# TIDA-01576_ADS8686S_ISO_Interface_Pg6-Le.net
KiCad netlist of a schematic drawn in Altium Designer
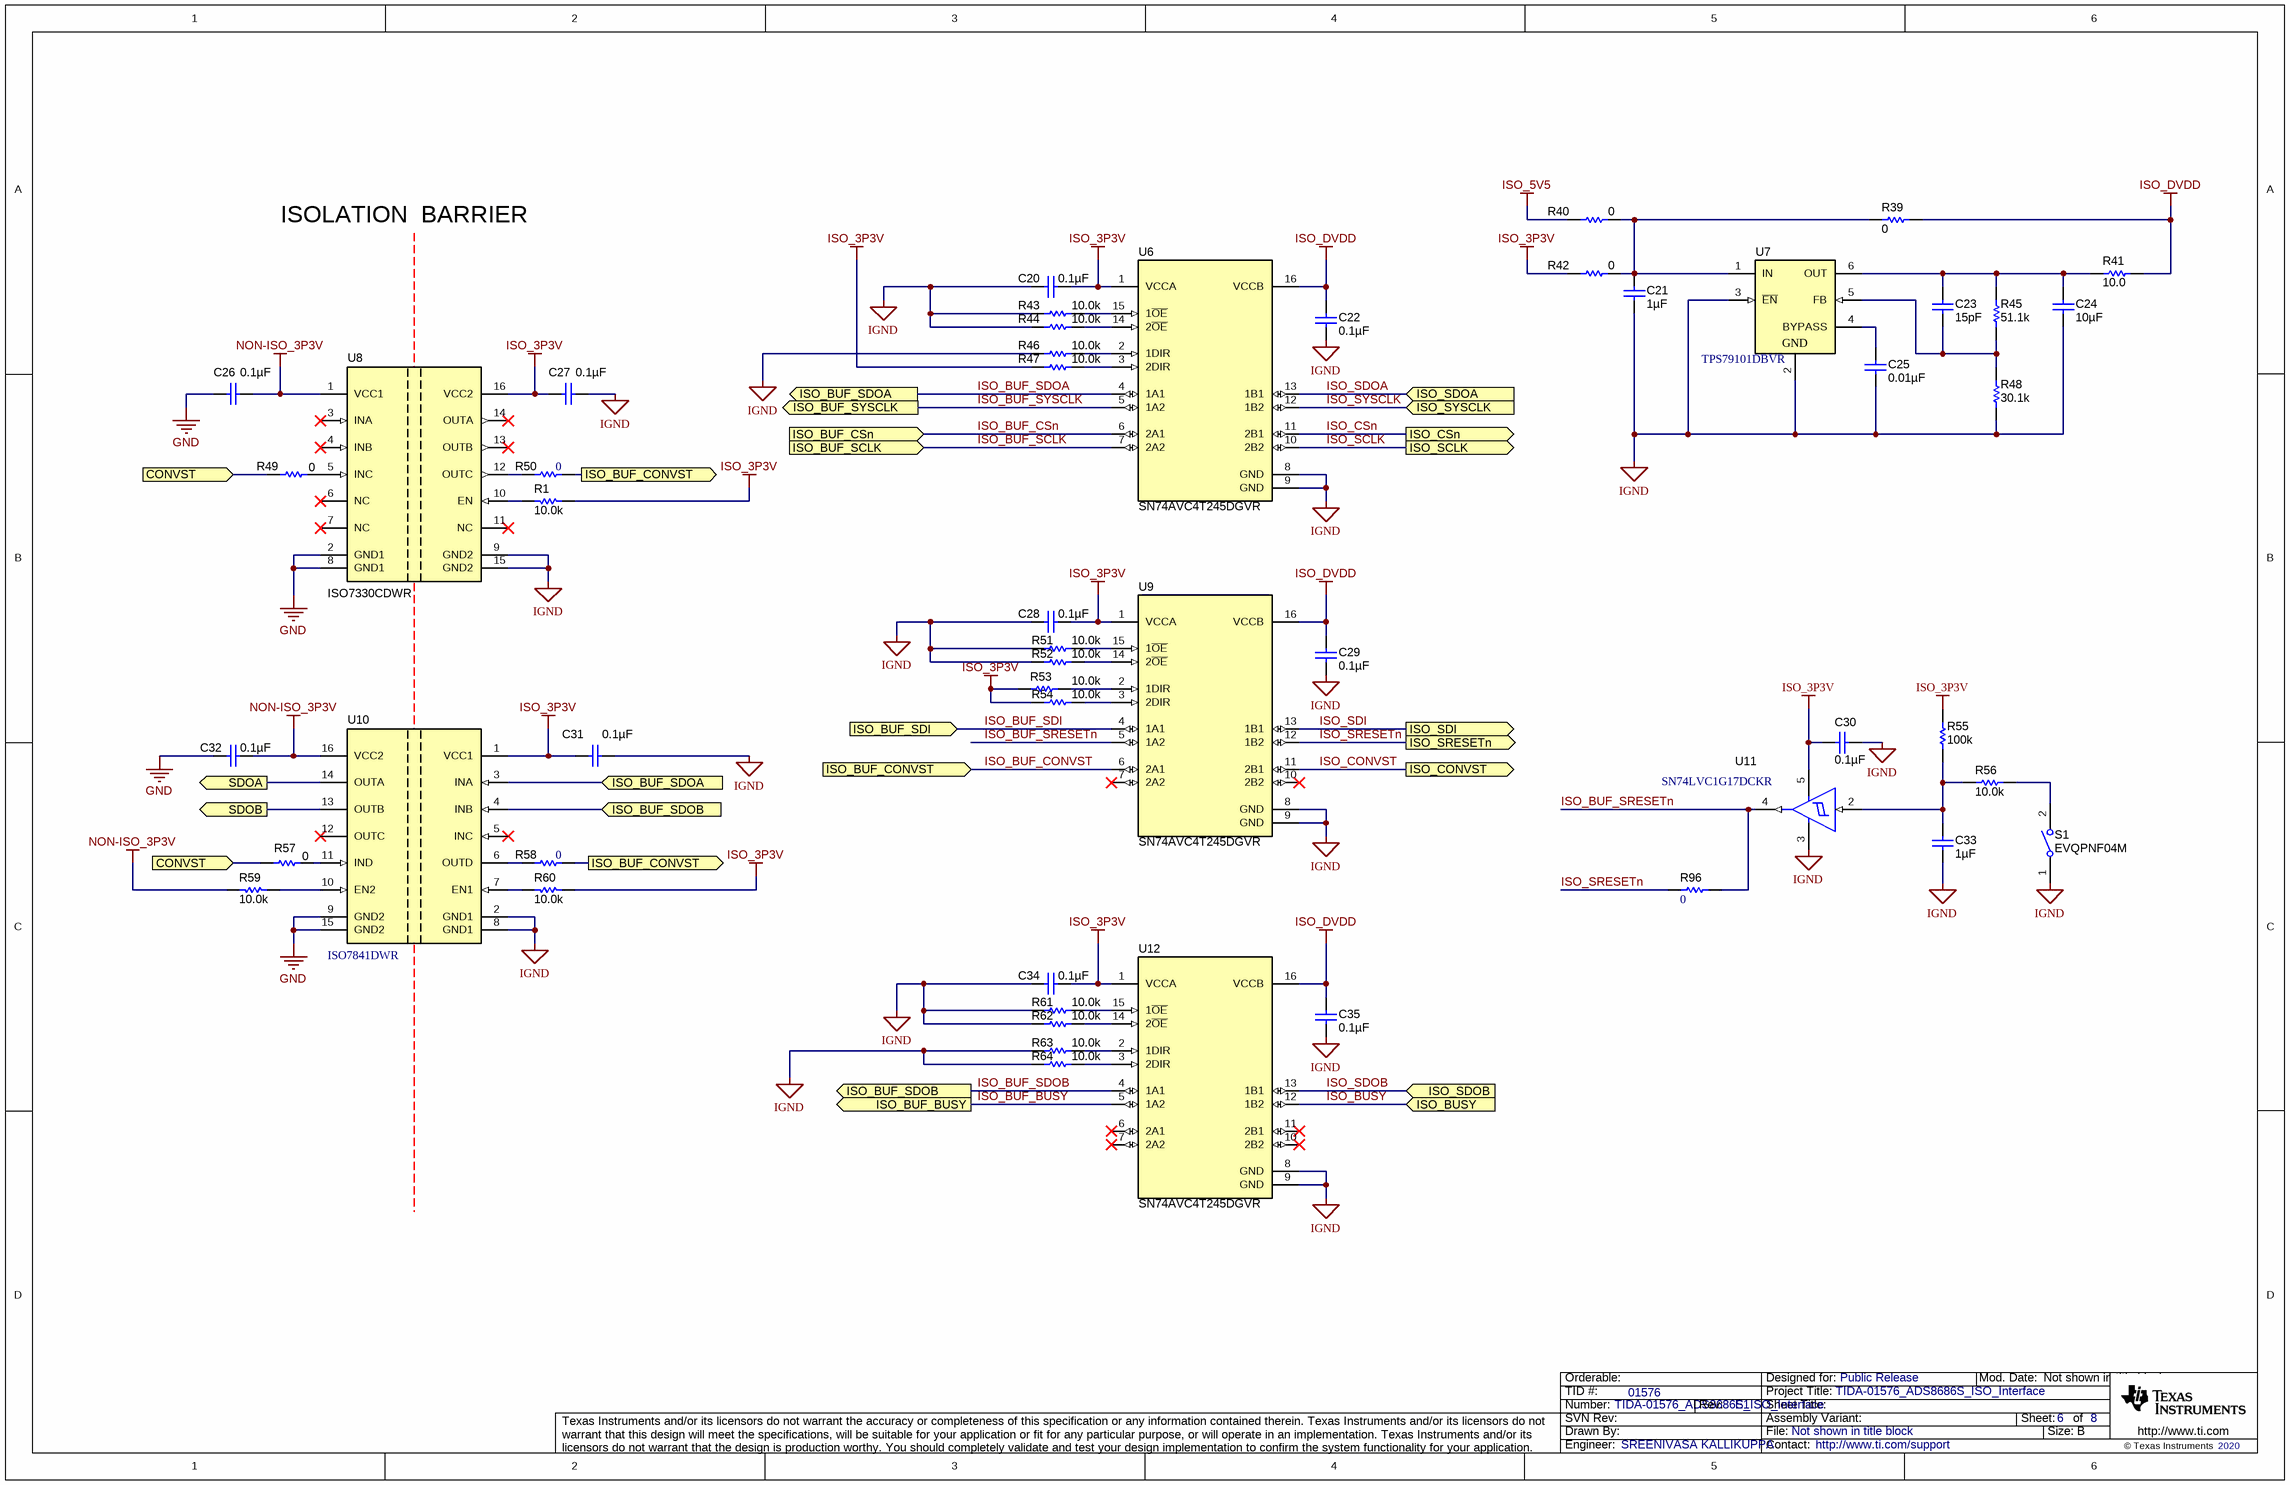
[diagram p0: TIDA-01576_ADS8686S_ISO_Interface_Pg6-LevelShifters.SchDoc]

(export (version "E")
  (design (tool "Eeschema 10.0.6"))
  (components
    (comp (ref "C20")
      (value "GRM155R71C104KA88D")
      (footprint "0402")
      (description "CAP, CERM, 0.1 µF, 16 V, +/- 10%, X7R, 0402")
      (fields
        (field (name "VALUEDISPLAYED") "0.1µF")
        (field (name "MANUFACTURER") "MuRata")
        (field (name "PUBLISHER") "Texas Instruments")
      )
      (libsource (lib "Capacitor_Ceramic") (part "GRM155R71C104KA88D"))
    )
    (comp (ref "C21")
      (value "GRM188R71E105KA12D")
      (footprint "0603")
      (description "CAP, CERM, 1 µF, 25 V, +/- 10%, X7R, 0603")
      (fields
        (field (name "VALUEDISPLAYED") "1µF")
        (field (name "MANUFACTURER") "MuRata")
        (field (name "PUBLISHER") "Texas Instruments")
      )
      (libsource (lib "Capacitor_Ceramic") (part "GRM188R71E105KA12D"))
    )
    (comp (ref "C22")
      (value "GRM155R71C104KA88D")
      (footprint "0402")
      (description "CAP, CERM, 0.1 µF, 16 V, +/- 10%, X7R, 0402")
      (fields
        (field (name "VALUEDISPLAYED") "0.1µF")
        (field (name "MANUFACTURER") "MuRata")
        (field (name "PUBLISHER") "Texas Instruments")
      )
      (libsource (lib "Capacitor_Ceramic") (part "GRM155R71C104KA88D"))
    )
    (comp (ref "C23")
      (value "GRM1885C1H150JA01D")
      (footprint "0603")
      (description "CAP, CERM, 15 pF, 50 V, +/- 5%, C0G/NP0, 0603")
      (fields
        (field (name "VALUEDISPLAYED") "15pF")
        (field (name "MANUFACTURER") "MuRata")
        (field (name "PUBLISHER") "Texas Instruments")
      )
      (libsource (lib "Capacitor_Ceramic") (part "GRM1885C1H150JA01D"))
    )
    (comp (ref "C24")
      (value "CL21B106KOQNNNE")
      (footprint "0805_HV")
      (description "CAP, CERM, 10 µF, 16 V, +/- 10%, X7R, 0805")
      (fields
        (field (name "VALUEDISPLAYED") "10µF")
        (field (name "MANUFACTURER") "Samsung Electro-Mechanics")
        (field (name "PUBLISHER") "Texas Instruments")
      )
      (libsource (lib "Capacitor_Ceramic") (part "CL21B106KOQNNNE"))
    )
    (comp (ref "C25")
      (value "GRM188R71E103KA01D")
      (footprint "0603")
      (description "CAP, CERM, 0.01 µF, 25 V, +/- 10%, X7R, 0603")
      (fields
        (field (name "VALUEDISPLAYED") "0.01µF")
        (field (name "MANUFACTURER") "MuRata")
        (field (name "PUBLISHER") "Texas Instruments")
      )
      (libsource (lib "Capacitor_Ceramic") (part "GRM188R71E103KA01D"))
    )
    (comp (ref "C26")
      (value "GRM155R71C104KA88D")
      (footprint "0402")
      (description "CAP, CERM, 0.1 µF, 16 V, +/- 10%, X7R, 0402")
      (fields
        (field (name "VALUEDISPLAYED") "0.1µF")
        (field (name "MANUFACTURER") "MuRata")
        (field (name "PUBLISHER") "Texas Instruments")
      )
      (libsource (lib "Capacitor_Ceramic") (part "GRM155R71C104KA88D"))
    )
    (comp (ref "C27")
      (value "GRM155R71C104KA88D")
      (footprint "0402")
      (description "CAP, CERM, 0.1 µF, 16 V, +/- 10%, X7R, 0402")
      (fields
        (field (name "VALUEDISPLAYED") "0.1µF")
        (field (name "MANUFACTURER") "MuRata")
        (field (name "PUBLISHER") "Texas Instruments")
      )
      (libsource (lib "Capacitor_Ceramic") (part "GRM155R71C104KA88D"))
    )
    (comp (ref "C28")
      (value "GRM155R71C104KA88D")
      (footprint "0402")
      (description "CAP, CERM, 0.1 µF, 16 V, +/- 10%, X7R, 0402")
      (fields
        (field (name "VALUEDISPLAYED") "0.1µF")
        (field (name "MANUFACTURER") "MuRata")
        (field (name "PUBLISHER") "Texas Instruments")
      )
      (libsource (lib "Capacitor_Ceramic") (part "GRM155R71C104KA88D"))
    )
    (comp (ref "C29")
      (value "GRM155R71C104KA88D")
      (footprint "0402")
      (description "CAP, CERM, 0.1 µF, 16 V, +/- 10%, X7R, 0402")
      (fields
        (field (name "VALUEDISPLAYED") "0.1µF")
        (field (name "MANUFACTURER") "MuRata")
        (field (name "PUBLISHER") "Texas Instruments")
      )
      (libsource (lib "Capacitor_Ceramic") (part "GRM155R71C104KA88D"))
    )
    (comp (ref "C30")
      (value "GRM155R71C104KA88D")
      (footprint "0402")
      (description "CAP, CERM, 0.1 µF, 16 V, +/- 10%, X7R, 0402")
      (fields
        (field (name "VALUEDISPLAYED") "0.1µF")
        (field (name "MANUFACTURER") "MuRata")
        (field (name "PUBLISHER") "Texas Instruments")
      )
      (libsource (lib "Capacitor_Ceramic") (part "GRM155R71C104KA88D"))
    )
    (comp (ref "C31")
      (value "GRM155R71C104KA88D")
      (footprint "0402")
      (description "CAP, CERM, 0.1 µF, 16 V, +/- 10%, X7R, 0402")
      (fields
        (field (name "VALUEDISPLAYED") "0.1µF")
        (field (name "MANUFACTURER") "MuRata")
        (field (name "PUBLISHER") "Texas Instruments")
      )
      (libsource (lib "Capacitor_Ceramic") (part "GRM155R71C104KA88D"))
    )
    (comp (ref "C32")
      (value "GRM155R71C104KA88D")
      (footprint "0402")
      (description "CAP, CERM, 0.1 µF, 16 V, +/- 10%, X7R, 0402")
      (fields
        (field (name "VALUEDISPLAYED") "0.1µF")
        (field (name "MANUFACTURER") "MuRata")
        (field (name "PUBLISHER") "Texas Instruments")
      )
      (libsource (lib "Capacitor_Ceramic") (part "GRM155R71C104KA88D"))
    )
    (comp (ref "C33")
      (value "GRM188R71E105KA12D")
      (footprint "0603")
      (description "CAP, CERM, 1 µF, 25 V, +/- 10%, X7R, 0603")
      (fields
        (field (name "VALUEDISPLAYED") "1µF")
        (field (name "MANUFACTURER") "MuRata")
        (field (name "PUBLISHER") "Texas Instruments")
      )
      (libsource (lib "Capacitor_Ceramic") (part "GRM188R71E105KA12D"))
    )
    (comp (ref "C34")
      (value "GRM155R71C104KA88D")
      (footprint "0402")
      (description "CAP, CERM, 0.1 µF, 16 V, +/- 10%, X7R, 0402")
      (fields
        (field (name "VALUEDISPLAYED") "0.1µF")
        (field (name "MANUFACTURER") "MuRata")
        (field (name "PUBLISHER") "Texas Instruments")
      )
      (libsource (lib "Capacitor_Ceramic") (part "GRM155R71C104KA88D"))
    )
    (comp (ref "C35")
      (value "GRM155R71C104KA88D")
      (footprint "0402")
      (description "CAP, CERM, 0.1 µF, 16 V, +/- 10%, X7R, 0402")
      (fields
        (field (name "VALUEDISPLAYED") "0.1µF")
        (field (name "MANUFACTURER") "MuRata")
        (field (name "PUBLISHER") "Texas Instruments")
      )
      (libsource (lib "Capacitor_Ceramic") (part "GRM155R71C104KA88D"))
    )
    (comp (ref "R1")
      (value "ERJ-2RKF1002X")
      (footprint "0402")
      (description "RES, 10.0 k, 1%, 0.1 W, 0402")
      (fields
        (field (name "VALUEDISPLAYED") "10.0k")
        (field (name "MANUFACTURER") "Panasonic")
        (field (name "PUBLISHER") "Texas Instruments")
      )
      (libsource (lib "Resistor_0402") (part "ERJ-2RKF1002X"))
    )
    (comp (ref "R39")
      (value "CRCW06030000Z0EA")
      (footprint "0603")
      (description "RES, 0, 5%, 0.1 W, 0603")
      (fields
        (field (name "VALUEDISPLAYED") "0")
        (field (name "MANUFACTURER") "Vishay-Dale")
        (field (name "PUBLISHER") "Texas Instruments")
      )
      (libsource (lib "Resistor_0603") (part "CRCW06030000Z0EA"))
    )
    (comp (ref "R40")
      (value "CRCW06030000Z0EA")
      (footprint "0603")
      (description "RES, 0, 5%, 0.1 W, 0603")
      (fields
        (field (name "VALUEDISPLAYED") "0")
        (field (name "MANUFACTURER") "Vishay-Dale")
        (field (name "PUBLISHER") "Texas Instruments")
      )
      (libsource (lib "Resistor_0603") (part "CRCW06030000Z0EA"))
    )
    (comp (ref "R41")
      (value "CRT0603-BY-10R0ELF")
      (footprint "0603")
      (description "RES, 10.0, 0.1%, 0.1 W, 0603")
      (fields
        (field (name "VALUEDISPLAYED") "10.0")
        (field (name "MANUFACTURER") "Bourns")
        (field (name "PUBLISHER") "Texas Instruments")
      )
      (libsource (lib "Resistor_0603") (part "CRT0603-BY-10R0ELF"))
    )
    (comp (ref "R42")
      (value "CRCW06030000Z0EA")
      (footprint "0603")
      (description "RES, 0, 5%, 0.1 W, 0603")
      (fields
        (field (name "VALUEDISPLAYED") "0")
        (field (name "MANUFACTURER") "Vishay-Dale")
        (field (name "PUBLISHER") "Texas Instruments")
      )
      (libsource (lib "Resistor_0603") (part "CRCW06030000Z0EA"))
    )
    (comp (ref "R43")
      (value "ERJ-2RKF1002X")
      (footprint "0402")
      (description "RES, 10.0 k, 1%, 0.1 W, 0402")
      (fields
        (field (name "VALUEDISPLAYED") "10.0k")
        (field (name "MANUFACTURER") "Panasonic")
        (field (name "PUBLISHER") "Texas Instruments")
      )
      (libsource (lib "Resistor_0402") (part "ERJ-2RKF1002X"))
    )
    (comp (ref "R44")
      (value "ERJ-2RKF1002X")
      (footprint "0402")
      (description "RES, 10.0 k, 1%, 0.1 W, 0402")
      (fields
        (field (name "VALUEDISPLAYED") "10.0k")
        (field (name "MANUFACTURER") "Panasonic")
        (field (name "PUBLISHER") "Texas Instruments")
      )
      (libsource (lib "Resistor_0402") (part "ERJ-2RKF1002X"))
    )
    (comp (ref "R45")
      (value "CRCW060351K1FKEA")
      (footprint "0603")
      (description "RES, 51.1 k, 1%, 0.1 W, 0603")
      (fields
        (field (name "VALUEDISPLAYED") "51.1k")
        (field (name "MANUFACTURER") "Vishay-Dale")
        (field (name "PUBLISHER") "Texas Instruments")
      )
      (libsource (lib "Resistor_0603") (part "CRCW060351K1FKEA"))
    )
    (comp (ref "R46")
      (value "ERJ-2RKF1002X")
      (footprint "0402")
      (description "RES, 10.0 k, 1%, 0.1 W, 0402")
      (fields
        (field (name "VALUEDISPLAYED") "10.0k")
        (field (name "MANUFACTURER") "Panasonic")
        (field (name "PUBLISHER") "Texas Instruments")
      )
      (libsource (lib "Resistor_0402") (part "ERJ-2RKF1002X"))
    )
    (comp (ref "R47")
      (value "ERJ-2RKF1002X")
      (footprint "0402")
      (description "RES, 10.0 k, 1%, 0.1 W, 0402")
      (fields
        (field (name "VALUEDISPLAYED") "10.0k")
        (field (name "MANUFACTURER") "Panasonic")
        (field (name "PUBLISHER") "Texas Instruments")
      )
      (libsource (lib "Resistor_0402") (part "ERJ-2RKF1002X"))
    )
    (comp (ref "R48")
      (value "CRCW060330K1FKEA")
      (footprint "0603")
      (description "RES, 30.1 k, 1%, 0.1 W, 0603")
      (fields
        (field (name "VALUEDISPLAYED") "30.1k")
        (field (name "MANUFACTURER") "Vishay-Dale")
        (field (name "PUBLISHER") "Texas Instruments")
      )
      (libsource (lib "Resistor_0603") (part "CRCW060330K1FKEA"))
    )
    (comp (ref "R49")
      (value "ERJ-2GE0R00X")
      (footprint "0402")
      (description "RES, 0, 5%, 0.063 W, 0402")
      (fields
        (field (name "VALUEDISPLAYED") "0")
        (field (name "MANUFACTURER") "Panasonic")
        (field (name "PUBLISHER") "Texas Instruments")
      )
      (libsource (lib "Resistor_0402") (part "ERJ-2GE0R00X"))
    )
    (comp (ref "R50")
      (value "ERJ-2GE0R00X")
      (footprint "0402")
      (description "RES, 0, 5%, 0.1 W, AEC-Q200 Grade 0, 0402")
      (fields (field (name "MANUFACTURER") "Panasonic") (field (name "VALUEDISPLAYED") "0"))
      (libsource (lib "Altium Vault - TI") (part "Resistor"))
    )
    (comp (ref "R51")
      (value "ERJ-2RKF1002X")
      (footprint "0402")
      (description "RES, 10.0 k, 1%, 0.1 W, 0402")
      (fields
        (field (name "VALUEDISPLAYED") "10.0k")
        (field (name "MANUFACTURER") "Panasonic")
        (field (name "PUBLISHER") "Texas Instruments")
      )
      (libsource (lib "Resistor_0402") (part "ERJ-2RKF1002X"))
    )
    (comp (ref "R52")
      (value "ERJ-2RKF1002X")
      (footprint "0402")
      (description "RES, 10.0 k, 1%, 0.1 W, 0402")
      (fields
        (field (name "VALUEDISPLAYED") "10.0k")
        (field (name "MANUFACTURER") "Panasonic")
        (field (name "PUBLISHER") "Texas Instruments")
      )
      (libsource (lib "Resistor_0402") (part "ERJ-2RKF1002X"))
    )
    (comp (ref "R53")
      (value "ERJ-2RKF1002X")
      (footprint "0402")
      (description "RES, 10.0 k, 1%, 0.1 W, 0402")
      (fields
        (field (name "VALUEDISPLAYED") "10.0k")
        (field (name "MANUFACTURER") "Panasonic")
        (field (name "PUBLISHER") "Texas Instruments")
      )
      (libsource (lib "Resistor_0402") (part "ERJ-2RKF1002X"))
    )
    (comp (ref "R54")
      (value "ERJ-2RKF1002X")
      (footprint "0402")
      (description "RES, 10.0 k, 1%, 0.1 W, 0402")
      (fields
        (field (name "VALUEDISPLAYED") "10.0k")
        (field (name "MANUFACTURER") "Panasonic")
        (field (name "PUBLISHER") "Texas Instruments")
      )
      (libsource (lib "Resistor_0402") (part "ERJ-2RKF1002X"))
    )
    (comp (ref "R55")
      (value "CRCW0402100KFKED")
      (footprint "0402")
      (description "RES, 100 k, 1%, 0.063 W, 0402")
      (fields
        (field (name "VALUEDISPLAYED") "100k")
        (field (name "MANUFACTURER") "Vishay-Dale")
        (field (name "PUBLISHER") "Texas Instruments")
      )
      (libsource (lib "Resistor_0402") (part "CRCW0402100KFKED"))
    )
    (comp (ref "R56")
      (value "ERJ-2RKF1002X")
      (footprint "0402")
      (description "RES, 10.0 k, 1%, 0.1 W, 0402")
      (fields
        (field (name "VALUEDISPLAYED") "10.0k")
        (field (name "MANUFACTURER") "Panasonic")
        (field (name "PUBLISHER") "Texas Instruments")
      )
      (libsource (lib "Resistor_0402") (part "ERJ-2RKF1002X"))
    )
    (comp (ref "R57")
      (value "ERJ-2GE0R00X")
      (footprint "0402")
      (description "RES, 0, 5%, 0.063 W, 0402")
      (fields
        (field (name "VALUEDISPLAYED") "0")
        (field (name "MANUFACTURER") "Panasonic")
        (field (name "PUBLISHER") "Texas Instruments")
      )
      (libsource (lib "Resistor_0402") (part "ERJ-2GE0R00X"))
    )
    (comp (ref "R58")
      (value "ERJ-2GE0R00X")
      (footprint "0402")
      (description "RES, 0, 5%, 0.1 W, AEC-Q200 Grade 0, 0402")
      (fields (field (name "MANUFACTURER") "Panasonic") (field (name "VALUEDISPLAYED") "0"))
      (libsource (lib "Altium Vault - TI") (part "Resistor"))
    )
    (comp (ref "R59")
      (value "ERJ-2RKF1002X")
      (footprint "0402")
      (description "RES, 10.0 k, 1%, 0.1 W, 0402")
      (fields
        (field (name "VALUEDISPLAYED") "10.0k")
        (field (name "MANUFACTURER") "Panasonic")
        (field (name "PUBLISHER") "Texas Instruments")
      )
      (libsource (lib "Resistor_0402") (part "ERJ-2RKF1002X"))
    )
    (comp (ref "R60")
      (value "ERJ-2RKF1002X")
      (footprint "0402")
      (description "RES, 10.0 k, 1%, 0.1 W, 0402")
      (fields
        (field (name "VALUEDISPLAYED") "10.0k")
        (field (name "MANUFACTURER") "Panasonic")
        (field (name "PUBLISHER") "Texas Instruments")
      )
      (libsource (lib "Resistor_0402") (part "ERJ-2RKF1002X"))
    )
    (comp (ref "R61")
      (value "ERJ-2RKF1002X")
      (footprint "0402")
      (description "RES, 10.0 k, 1%, 0.1 W, 0402")
      (fields
        (field (name "VALUEDISPLAYED") "10.0k")
        (field (name "MANUFACTURER") "Panasonic")
        (field (name "PUBLISHER") "Texas Instruments")
      )
      (libsource (lib "Resistor_0402") (part "ERJ-2RKF1002X"))
    )
    (comp (ref "R62")
      (value "ERJ-2RKF1002X")
      (footprint "0402")
      (description "RES, 10.0 k, 1%, 0.1 W, 0402")
      (fields
        (field (name "VALUEDISPLAYED") "10.0k")
        (field (name "MANUFACTURER") "Panasonic")
        (field (name "PUBLISHER") "Texas Instruments")
      )
      (libsource (lib "Resistor_0402") (part "ERJ-2RKF1002X"))
    )
    (comp (ref "R63")
      (value "ERJ-2RKF1002X")
      (footprint "0402")
      (description "RES, 10.0 k, 1%, 0.1 W, 0402")
      (fields
        (field (name "VALUEDISPLAYED") "10.0k")
        (field (name "MANUFACTURER") "Panasonic")
        (field (name "PUBLISHER") "Texas Instruments")
      )
      (libsource (lib "Resistor_0402") (part "ERJ-2RKF1002X"))
    )
    (comp (ref "R64")
      (value "ERJ-2RKF1002X")
      (footprint "0402")
      (description "RES, 10.0 k, 1%, 0.1 W, 0402")
      (fields
        (field (name "VALUEDISPLAYED") "10.0k")
        (field (name "MANUFACTURER") "Panasonic")
        (field (name "PUBLISHER") "Texas Instruments")
      )
      (libsource (lib "Resistor_0402") (part "ERJ-2RKF1002X"))
    )
    (comp (ref "R96")
      (value "CRCW06030000Z0EA")
      (footprint "0603")
      (description "RES, 0, 5%, 0.1 W, 0603")
      (fields
        (field (name "MANUFACTURER") "Vishay-Dale")
        (field (name "VALUEDISPLAYED") "0")
        (field (name "PUBLISHER") "Texas Instruments")
      )
      (libsource (lib "Altium Vault - TI") (part "Resistor"))
    )
    (comp (ref "S1")
      (value "EVQPNF04M")
      (footprint "SW_EVQPNF04M")
      (description "Switch, Tactile, SPST-NO, 0.05A, 12V, SMD")
      (fields
        (field (name "MANUFACTURER") "Panasonic")
        (field (name "SYMBOLCREATOR") "a0799628")
        (field (name "PUBLISHER") "Texas Instruments")
      )
      (libsource (lib "Switches") (part "EVQPNF04M"))
    )
    (comp (ref "U6")
      (value "SN74AVC4T245DGVR")
      (footprint "DGV0016A_N")
      (fields
        (field (name "MANUFACTURER") "Texas Instruments")
        (field (name "SYMBOLCREATOR") "Altium")
        (field (name "PUBLISHER") "Texas Instruments")
      )
      (libsource (lib "TIDA-01035-E1") (part "SN74AVC4T245DGVR"))
    )
    (comp (ref "U7")
      (value "TPS79101DBVR")
      (footprint "DBV0006A_N")
      (fields
        (field (name "MANUFACTURER") "Texas Instruments")
        (field (name "ALTERNATE PARTNUMBER") "Equivalent")
      )
      (libsource (lib "TI Power Management Linear Regulator Single Channel LDO (0-350mA)") (part "TPS79101DBVR"))
    )
    (comp (ref "U8")
      (value "ISO7330CDWR")
      (footprint "DW0016B_HV")
      (description "Robust EMC, Low Power, Triple-Channel 3/0 Digital Isolator, Fail-Safe High, DW0016B (SOIC-16)")
      (fields
        (field (name "ALTERNATE PARTNUMBER") "ISO7330CDW")
        (field (name "MANUFACTURER") "Texas Instruments")
        (field (name "SYMBOLCREATOR") "Altium")
        (field (name "PUBLISHER") "Texas Instruments")
      )
      (libsource (lib "TI_Pre_Release") (part "ISO7330CDWR"))
    )
    (comp (ref "U9")
      (value "SN74AVC4T245DGVR")
      (footprint "DGV0016A_N")
      (fields
        (field (name "MANUFACTURER") "Texas Instruments")
        (field (name "SYMBOLCREATOR") "Altium")
        (field (name "PUBLISHER") "Texas Instruments")
      )
      (libsource (lib "TIDA-01035-E1") (part "SN74AVC4T245DGVR"))
    )
    (comp (ref "U10")
      (value "ISO7841DWR")
      (footprint "DW0016B_HV")
      (description "High-Immunity, 5.7kVRMS Reinforced Quad-Channel 3/1 Digital Isolator, 100Mbps, DW0016B (SOIC-16)")
      (fields
        (field (name "ALTERNATE PARTNUMBER") "ISO7841DW")
        (field (name "MANUFACTURER") "Texas Instruments")
        (field (name "PARTNUMBER") "ISO7841DWR")
      )
      (libsource (lib "Altium Vault - TI") (part "ISO7841"))
    )
    (comp (ref "U11")
      (value "SN74LVC1G17DCKR")
      (footprint "DCK0005A_L")
      (description "SINGLE SCHMITT-TRIGGER BUFFER, DCK0005A")
      (fields
        (field (name "ALTERNATE PARTNUMBER") "SN74LVC1G17DCKT")
        (field (name "MANUFACTURER") "Texas Instruments")
        (field (name "SYMBOLCREATOR") "a0799628")
        (field (name "PUBLISHER") "Texas Instruments")
      )
      (libsource (lib "TI_Pre_Release") (part "SN74LVC1G17DCKR"))
    )
    (comp (ref "U12")
      (value "SN74AVC4T245DGVR")
      (footprint "DGV0016A_N")
      (fields
        (field (name "MANUFACTURER") "Texas Instruments")
        (field (name "SYMBOLCREATOR") "Altium")
        (field (name "PUBLISHER") "Texas Instruments")
      )
      (libsource (lib "TIDA-01035-E1") (part "SN74AVC4T245DGVR"))
    )
  )
  (nets
    (net (code "1") (name "/CONVST") (class "Default")
      (node (ref "R49") (pin "1") (pinfunction "1_1") (pintype "passive"))
      (node (ref "R57") (pin "1") (pinfunction "1_1") (pintype "passive"))
    )
    (net (code "2") (name "/ISO_BUF_BUSY") (class "Default")
      (node (ref "U12") (pin "5") (pinfunction "1A2_5") (pintype "bidirectional"))
    )
    (net (code "3") (name "/ISO_BUF_CONVST") (class "Default")
      (node (ref "R50") (pin "2") (pinfunction "2_2") (pintype "passive"))
      (node (ref "R58") (pin "2") (pinfunction "2_2") (pintype "passive"))
      (node (ref "U9") (pin "6") (pinfunction "2A1_6") (pintype "bidirectional"))
    )
    (net (code "4") (name "/ISO_BUF_CSn") (class "Default")
      (node (ref "U6") (pin "6") (pinfunction "2A1_6") (pintype "bidirectional"))
    )
    (net (code "5") (name "/ISO_BUF_SCLK") (class "Default")
      (node (ref "U6") (pin "7") (pinfunction "2A2_7") (pintype "bidirectional"))
    )
    (net (code "6") (name "/ISO_BUF_SDI") (class "Default")
      (node (ref "U9") (pin "4") (pinfunction "1A1_4") (pintype "bidirectional"))
    )
    (net (code "7") (name "/ISO_BUF_SDOA") (class "Default")
      (node (ref "U10") (pin "3") (pinfunction "INA_3") (pintype "input"))
      (node (ref "U6") (pin "4") (pinfunction "1A1_4") (pintype "bidirectional"))
    )
    (net (code "8") (name "/ISO_BUF_SDOB") (class "Default")
      (node (ref "U10") (pin "4") (pinfunction "INB_4") (pintype "input"))
      (node (ref "U12") (pin "4") (pinfunction "1A1_4") (pintype "bidirectional"))
    )
    (net (code "9") (name "/ISO_BUF_SRESETn") (class "Default")
      (node (ref "R96") (pin "1") (pinfunction "1_1") (pintype "passive"))
      (node (ref "U11") (pin "4") (pinfunction "Y_4") (pintype "output"))
      (node (ref "U9") (pin "5") (pinfunction "1A2_5") (pintype "bidirectional"))
    )
    (net (code "10") (name "/ISO_BUF_SYSCLK") (class "Default")
      (node (ref "U6") (pin "5") (pinfunction "1A2_5") (pintype "bidirectional"))
    )
    (net (code "11") (name "/ISO_BUSY") (class "Default")
      (node (ref "U12") (pin "12") (pinfunction "1B2_12") (pintype "bidirectional"))
    )
    (net (code "12") (name "/ISO_CONVST") (class "Default")
      (node (ref "U9") (pin "11") (pinfunction "2B1_11") (pintype "bidirectional"))
    )
    (net (code "13") (name "/ISO_CSn") (class "Default")
      (node (ref "U6") (pin "11") (pinfunction "2B1_11") (pintype "bidirectional"))
    )
    (net (code "14") (name "/ISO_SCLK") (class "Default")
      (node (ref "U6") (pin "10") (pinfunction "2B2_10") (pintype "bidirectional"))
    )
    (net (code "15") (name "/ISO_SDI") (class "Default")
      (node (ref "U9") (pin "13") (pinfunction "1B1_13") (pintype "bidirectional"))
    )
    (net (code "16") (name "/ISO_SDOA") (class "Default")
      (node (ref "U6") (pin "13") (pinfunction "1B1_13") (pintype "bidirectional"))
    )
    (net (code "17") (name "/ISO_SDOB") (class "Default")
      (node (ref "U12") (pin "13") (pinfunction "1B1_13") (pintype "bidirectional"))
    )
    (net (code "18") (name "/ISO_SRESETn") (class "Default")
      (node (ref "R96") (pin "2") (pinfunction "2_2") (pintype "passive"))
      (node (ref "U9") (pin "12") (pinfunction "1B2_12") (pintype "bidirectional"))
    )
    (net (code "19") (name "/ISO_SYSCLK") (class "Default")
      (node (ref "U6") (pin "12") (pinfunction "1B2_12") (pintype "bidirectional"))
    )
    (net (code "20") (name "/SDOA") (class "Default")
      (node (ref "U10") (pin "14") (pinfunction "OUTA_14") (pintype "tri_state"))
    )
    (net (code "21") (name "/SDOB") (class "Default")
      (node (ref "U10") (pin "13") (pinfunction "OUTB_13") (pintype "tri_state"))
    )
    (net (code "22") (name "GND") (class "Default")
      (node (ref "C26") (pin "1") (pinfunction "1_1") (pintype "passive"))
      (node (ref "C32") (pin "2") (pinfunction "2_2") (pintype "passive"))
      (node (ref "U10") (pin "15") (pinfunction "GND2_15") (pintype "power_in"))
      (node (ref "U10") (pin "9") (pinfunction "GND2_9") (pintype "power_in"))
      (node (ref "U8") (pin "2") (pinfunction "GND1_2") (pintype "power_in"))
      (node (ref "U8") (pin "8") (pinfunction "GND1_8") (pintype "power_in"))
    )
    (net (code "23") (name "IGND") (class "Default")
      (node (ref "C20") (pin "2") (pinfunction "2_2") (pintype "passive"))
      (node (ref "C21") (pin "1") (pinfunction "1_1") (pintype "passive"))
      (node (ref "C22") (pin "2") (pinfunction "2_2") (pintype "passive"))
      (node (ref "C24") (pin "2") (pinfunction "2_2") (pintype "passive"))
      (node (ref "C25") (pin "2") (pinfunction "2_2") (pintype "passive"))
      (node (ref "C27") (pin "2") (pinfunction "2_2") (pintype "passive"))
      (node (ref "C28") (pin "2") (pinfunction "2_2") (pintype "passive"))
      (node (ref "C29") (pin "2") (pinfunction "2_2") (pintype "passive"))
      (node (ref "C30") (pin "1") (pinfunction "1_1") (pintype "passive"))
      (node (ref "C31") (pin "1") (pinfunction "1_1") (pintype "passive"))
      (node (ref "C33") (pin "2") (pinfunction "2_2") (pintype "passive"))
      (node (ref "C34") (pin "2") (pinfunction "2_2") (pintype "passive"))
      (node (ref "C35") (pin "2") (pinfunction "2_2") (pintype "passive"))
      (node (ref "R43") (pin "1") (pinfunction "1_1") (pintype "passive"))
      (node (ref "R44") (pin "1") (pinfunction "1_1") (pintype "passive"))
      (node (ref "R46") (pin "2") (pinfunction "2_2") (pintype "passive"))
      (node (ref "R48") (pin "1") (pinfunction "1_1") (pintype "passive"))
      (node (ref "R51") (pin "1") (pinfunction "1_1") (pintype "passive"))
      (node (ref "R52") (pin "1") (pinfunction "1_1") (pintype "passive"))
      (node (ref "R61") (pin "1") (pinfunction "1_1") (pintype "passive"))
      (node (ref "R62") (pin "1") (pinfunction "1_1") (pintype "passive"))
      (node (ref "R63") (pin "1") (pinfunction "1_1") (pintype "passive"))
      (node (ref "R64") (pin "1") (pinfunction "1_1") (pintype "passive"))
      (node (ref "S1") (pin "1") (pinfunction "1_1") (pintype "passive"))
      (node (ref "U10") (pin "2") (pinfunction "GND1_2") (pintype "power_in"))
      (node (ref "U10") (pin "8") (pinfunction "GND1_8") (pintype "power_in"))
      (node (ref "U11") (pin "3") (pinfunction "GND_3") (pintype "power_in"))
      (node (ref "U12") (pin "8") (pinfunction "GND_8") (pintype "power_in"))
      (node (ref "U12") (pin "9") (pinfunction "GND_9") (pintype "power_in"))
      (node (ref "U6") (pin "8") (pinfunction "GND_8") (pintype "power_in"))
      (node (ref "U6") (pin "9") (pinfunction "GND_9") (pintype "power_in"))
      (node (ref "U7") (pin "2") (pinfunction "GND_2") (pintype "power_in"))
      (node (ref "U7") (pin "3") (pinfunction "~{EN}_3") (pintype "input"))
      (node (ref "U8") (pin "15") (pinfunction "GND2_15") (pintype "power_in"))
      (node (ref "U8") (pin "9") (pinfunction "GND2_9") (pintype "power_in"))
      (node (ref "U9") (pin "8") (pinfunction "GND_8") (pintype "power_in"))
      (node (ref "U9") (pin "9") (pinfunction "GND_9") (pintype "power_in"))
    )
    (net (code "24") (name "ISO_3P3V") (class "Default")
      (node (ref "C20") (pin "1") (pinfunction "1_1") (pintype "passive"))
      (node (ref "C27") (pin "1") (pinfunction "1_1") (pintype "passive"))
      (node (ref "C28") (pin "1") (pinfunction "1_1") (pintype "passive"))
      (node (ref "C30") (pin "2") (pinfunction "2_2") (pintype "passive"))
      (node (ref "C31") (pin "2") (pinfunction "2_2") (pintype "passive"))
      (node (ref "C34") (pin "1") (pinfunction "1_1") (pintype "passive"))
      (node (ref "R1") (pin "1") (pinfunction "1_1") (pintype "passive"))
      (node (ref "R42") (pin "2") (pinfunction "2_2") (pintype "passive"))
      (node (ref "R47") (pin "2") (pinfunction "2_2") (pintype "passive"))
      (node (ref "R53") (pin "2") (pinfunction "2_2") (pintype "passive"))
      (node (ref "R54") (pin "1") (pinfunction "1_1") (pintype "passive"))
      (node (ref "R55") (pin "2") (pinfunction "2_2") (pintype "passive"))
      (node (ref "R60") (pin "1") (pinfunction "1_1") (pintype "passive"))
      (node (ref "U10") (pin "1") (pinfunction "VCC1_1") (pintype "power_in"))
      (node (ref "U11") (pin "5") (pinfunction "VCC_5") (pintype "power_in"))
      (node (ref "U12") (pin "1") (pinfunction "VCCA_1") (pintype "power_in"))
      (node (ref "U6") (pin "1") (pinfunction "VCCA_1") (pintype "power_in"))
      (node (ref "U8") (pin "16") (pinfunction "VCC2_16") (pintype "power_in"))
      (node (ref "U9") (pin "1") (pinfunction "VCCA_1") (pintype "power_in"))
    )
    (net (code "25") (name "ISO_5V5") (class "Default")
      (node (ref "R40") (pin "2") (pinfunction "2_2") (pintype "passive"))
    )
    (net (code "26") (name "ISO_DVDD") (class "Default")
      (node (ref "C22") (pin "1") (pinfunction "1_1") (pintype "passive"))
      (node (ref "C29") (pin "1") (pinfunction "1_1") (pintype "passive"))
      (node (ref "C35") (pin "1") (pinfunction "1_1") (pintype "passive"))
      (node (ref "R39") (pin "1") (pinfunction "1_1") (pintype "passive"))
      (node (ref "R41") (pin "1") (pinfunction "1_1") (pintype "passive"))
      (node (ref "U12") (pin "16") (pinfunction "VCCB_16") (pintype "power_in"))
      (node (ref "U6") (pin "16") (pinfunction "VCCB_16") (pintype "power_in"))
      (node (ref "U9") (pin "16") (pinfunction "VCCB_16") (pintype "power_in"))
    )
    (net (code "27") (name "NON-ISO_3P3V") (class "Default")
      (node (ref "C26") (pin "2") (pinfunction "2_2") (pintype "passive"))
      (node (ref "C32") (pin "1") (pinfunction "1_1") (pintype "passive"))
      (node (ref "R59") (pin "2") (pinfunction "2_2") (pintype "passive"))
      (node (ref "U10") (pin "16") (pinfunction "VCC2_16") (pintype "power_in"))
      (node (ref "U8") (pin "1") (pinfunction "VCC1_1") (pintype "power_in"))
    )
    (net (code "28") (name "Net-(R56-Pad2)") (class "Default")
      (node (ref "R56") (pin "2") (pinfunction "2_2") (pintype "passive"))
      (node (ref "S1") (pin "2") (pinfunction "2_2") (pintype "passive"))
    )
    (net (code "29") (name "Net-(U6-1DIR)") (class "Default")
      (node (ref "R46") (pin "1") (pinfunction "1_1") (pintype "passive"))
      (node (ref "U6") (pin "2") (pinfunction "1DIR_2") (pintype "input"))
    )
    (net (code "30") (name "Net-(U6-1~{OE})") (class "Default")
      (node (ref "R43") (pin "2") (pinfunction "2_2") (pintype "passive"))
      (node (ref "U6") (pin "15") (pinfunction "1~{OE}_15") (pintype "input"))
    )
    (net (code "31") (name "Net-(U6-2DIR)") (class "Default")
      (node (ref "R47") (pin "1") (pinfunction "1_1") (pintype "passive"))
      (node (ref "U6") (pin "3") (pinfunction "2DIR_3") (pintype "input"))
    )
    (net (code "32") (name "Net-(U6-2~{OE})") (class "Default")
      (node (ref "R44") (pin "2") (pinfunction "2_2") (pintype "passive"))
      (node (ref "U6") (pin "14") (pinfunction "2~{OE}_14") (pintype "input"))
    )
    (net (code "33") (name "Net-(U7-BYPASS)") (class "Default")
      (node (ref "C25") (pin "1") (pinfunction "1_1") (pintype "passive"))
      (node (ref "U7") (pin "4") (pinfunction "BYPASS_4") (pintype "passive"))
    )
    (net (code "34") (name "Net-(U7-FB)") (class "Default")
      (node (ref "C23") (pin "2") (pinfunction "2_2") (pintype "passive"))
      (node (ref "R45") (pin "1") (pinfunction "1_1") (pintype "passive"))
      (node (ref "R48") (pin "2") (pinfunction "2_2") (pintype "passive"))
      (node (ref "U7") (pin "5") (pinfunction "FB_5") (pintype "input"))
    )
    (net (code "35") (name "Net-(U7-IN)") (class "Default")
      (node (ref "C21") (pin "2") (pinfunction "2_2") (pintype "passive"))
      (node (ref "R39") (pin "2") (pinfunction "2_2") (pintype "passive"))
      (node (ref "R40") (pin "1") (pinfunction "1_1") (pintype "passive"))
      (node (ref "R42") (pin "1") (pinfunction "1_1") (pintype "passive"))
      (node (ref "U7") (pin "1") (pinfunction "IN_1") (pintype "power_in"))
    )
    (net (code "36") (name "Net-(U7-OUT)") (class "Default")
      (node (ref "C23") (pin "1") (pinfunction "1_1") (pintype "passive"))
      (node (ref "C24") (pin "1") (pinfunction "1_1") (pintype "passive"))
      (node (ref "R41") (pin "2") (pinfunction "2_2") (pintype "passive"))
      (node (ref "R45") (pin "2") (pinfunction "2_2") (pintype "passive"))
      (node (ref "U7") (pin "6") (pinfunction "OUT_6") (pintype "power_in"))
    )
    (net (code "37") (name "Net-(U8-EN)") (class "Default")
      (node (ref "R1") (pin "2") (pinfunction "2_2") (pintype "passive"))
      (node (ref "U8") (pin "10") (pinfunction "EN_10") (pintype "input"))
    )
    (net (code "38") (name "Net-(U8-INC)") (class "Default")
      (node (ref "R49") (pin "2") (pinfunction "2_2") (pintype "passive"))
      (node (ref "U8") (pin "5") (pinfunction "INC_5") (pintype "input"))
    )
    (net (code "39") (name "Net-(U8-OUTC)") (class "Default")
      (node (ref "R50") (pin "1") (pinfunction "1_1") (pintype "passive"))
      (node (ref "U8") (pin "12") (pinfunction "OUTC_12") (pintype "output"))
    )
    (net (code "40") (name "Net-(U9-1DIR)") (class "Default")
      (node (ref "R53") (pin "1") (pinfunction "1_1") (pintype "passive"))
      (node (ref "U9") (pin "2") (pinfunction "1DIR_2") (pintype "input"))
    )
    (net (code "41") (name "Net-(U9-1~{OE})") (class "Default")
      (node (ref "R51") (pin "2") (pinfunction "2_2") (pintype "passive"))
      (node (ref "U9") (pin "15") (pinfunction "1~{OE}_15") (pintype "input"))
    )
    (net (code "42") (name "Net-(U9-2DIR)") (class "Default")
      (node (ref "R54") (pin "2") (pinfunction "2_2") (pintype "passive"))
      (node (ref "U9") (pin "3") (pinfunction "2DIR_3") (pintype "input"))
    )
    (net (code "43") (name "Net-(U9-2~{OE})") (class "Default")
      (node (ref "R52") (pin "2") (pinfunction "2_2") (pintype "passive"))
      (node (ref "U9") (pin "14") (pinfunction "2~{OE}_14") (pintype "input"))
    )
    (net (code "44") (name "Net-(U10-EN1)") (class "Default")
      (node (ref "R60") (pin "2") (pinfunction "2_2") (pintype "passive"))
      (node (ref "U10") (pin "7") (pinfunction "EN1_7") (pintype "input"))
    )
    (net (code "45") (name "Net-(U10-EN2)") (class "Default")
      (node (ref "R59") (pin "1") (pinfunction "1_1") (pintype "passive"))
      (node (ref "U10") (pin "10") (pinfunction "EN2_10") (pintype "input"))
    )
    (net (code "46") (name "Net-(U10-IND)") (class "Default")
      (node (ref "R57") (pin "2") (pinfunction "2_2") (pintype "passive"))
      (node (ref "U10") (pin "11") (pinfunction "IND_11") (pintype "input"))
    )
    (net (code "47") (name "Net-(U10-OUTD)") (class "Default")
      (node (ref "R58") (pin "1") (pinfunction "1_1") (pintype "passive"))
      (node (ref "U10") (pin "6") (pinfunction "OUTD_6") (pintype "tri_state"))
    )
    (net (code "48") (name "Net-(U11-A)") (class "Default")
      (node (ref "C33") (pin "1") (pinfunction "1_1") (pintype "passive"))
      (node (ref "R55") (pin "1") (pinfunction "1_1") (pintype "passive"))
      (node (ref "R56") (pin "1") (pinfunction "1_1") (pintype "passive"))
      (node (ref "U11") (pin "2") (pinfunction "A_2") (pintype "input"))
    )
    (net (code "49") (name "Net-(U12-1DIR)") (class "Default")
      (node (ref "R63") (pin "2") (pinfunction "2_2") (pintype "passive"))
      (node (ref "U12") (pin "2") (pinfunction "1DIR_2") (pintype "input"))
    )
    (net (code "50") (name "Net-(U12-1~{OE})") (class "Default")
      (node (ref "R61") (pin "2") (pinfunction "2_2") (pintype "passive"))
      (node (ref "U12") (pin "15") (pinfunction "1~{OE}_15") (pintype "input"))
    )
    (net (code "51") (name "Net-(U12-2DIR)") (class "Default")
      (node (ref "R64") (pin "2") (pinfunction "2_2") (pintype "passive"))
      (node (ref "U12") (pin "3") (pinfunction "2DIR_3") (pintype "input"))
    )
    (net (code "52") (name "Net-(U12-2~{OE})") (class "Default")
      (node (ref "R62") (pin "2") (pinfunction "2_2") (pintype "passive"))
      (node (ref "U12") (pin "14") (pinfunction "2~{OE}_14") (pintype "input"))
    )
    (net (code "53") (name "unconnected-(U8-INA-Pad3)") (class "Default")
      (node (ref "U8") (pin "3") (pinfunction "INA_3") (pintype "input+no_connect"))
    )
    (net (code "54") (name "unconnected-(U8-INB-Pad4)") (class "Default")
      (node (ref "U8") (pin "4") (pinfunction "INB_4") (pintype "input+no_connect"))
    )
    (net (code "55") (name "unconnected-(U8-NC-Pad6)") (class "Default")
      (node (ref "U8") (pin "6") (pinfunction "NC_6") (pintype "passive+no_connect"))
    )
    (net (code "56") (name "unconnected-(U8-NC-Pad7)") (class "Default")
      (node (ref "U8") (pin "7") (pinfunction "NC_7") (pintype "passive+no_connect"))
    )
    (net (code "57") (name "unconnected-(U8-NC-Pad11)") (class "Default")
      (node (ref "U8") (pin "11") (pinfunction "NC_11") (pintype "passive+no_connect"))
    )
    (net (code "58") (name "unconnected-(U8-OUTA-Pad14)") (class "Default")
      (node (ref "U8") (pin "14") (pinfunction "OUTA_14") (pintype "output+no_connect"))
    )
    (net (code "59") (name "unconnected-(U8-OUTB-Pad13)") (class "Default")
      (node (ref "U8") (pin "13") (pinfunction "OUTB_13") (pintype "output+no_connect"))
    )
    (net (code "60") (name "unconnected-(U9-2A2-Pad7)") (class "Default")
      (node (ref "U9") (pin "7") (pinfunction "2A2_7") (pintype "bidirectional+no_connect"))
    )
    (net (code "61") (name "unconnected-(U9-2B2-Pad10)") (class "Default")
      (node (ref "U9") (pin "10") (pinfunction "2B2_10") (pintype "bidirectional+no_connect"))
    )
    (net (code "62") (name "unconnected-(U10-INC-Pad5)") (class "Default")
      (node (ref "U10") (pin "5") (pinfunction "INC_5") (pintype "input+no_connect"))
    )
    (net (code "63") (name "unconnected-(U10-OUTC-Pad12)") (class "Default")
      (node (ref "U10") (pin "12") (pinfunction "OUTC_12") (pintype "tri_state+no_connect"))
    )
    (net (code "64") (name "unconnected-(U12-2A1-Pad6)") (class "Default")
      (node (ref "U12") (pin "6") (pinfunction "2A1_6") (pintype "bidirectional+no_connect"))
    )
    (net (code "65") (name "unconnected-(U12-2A2-Pad7)") (class "Default")
      (node (ref "U12") (pin "7") (pinfunction "2A2_7") (pintype "bidirectional+no_connect"))
    )
    (net (code "66") (name "unconnected-(U12-2B1-Pad11)") (class "Default")
      (node (ref "U12") (pin "11") (pinfunction "2B1_11") (pintype "bidirectional+no_connect"))
    )
    (net (code "67") (name "unconnected-(U12-2B2-Pad10)") (class "Default")
      (node (ref "U12") (pin "10") (pinfunction "2B2_10") (pintype "bidirectional+no_connect"))
    )
  )
)
